# C-01_CPU_PWR.net
KiCad netlist of a schematic drawn in Altium Designer
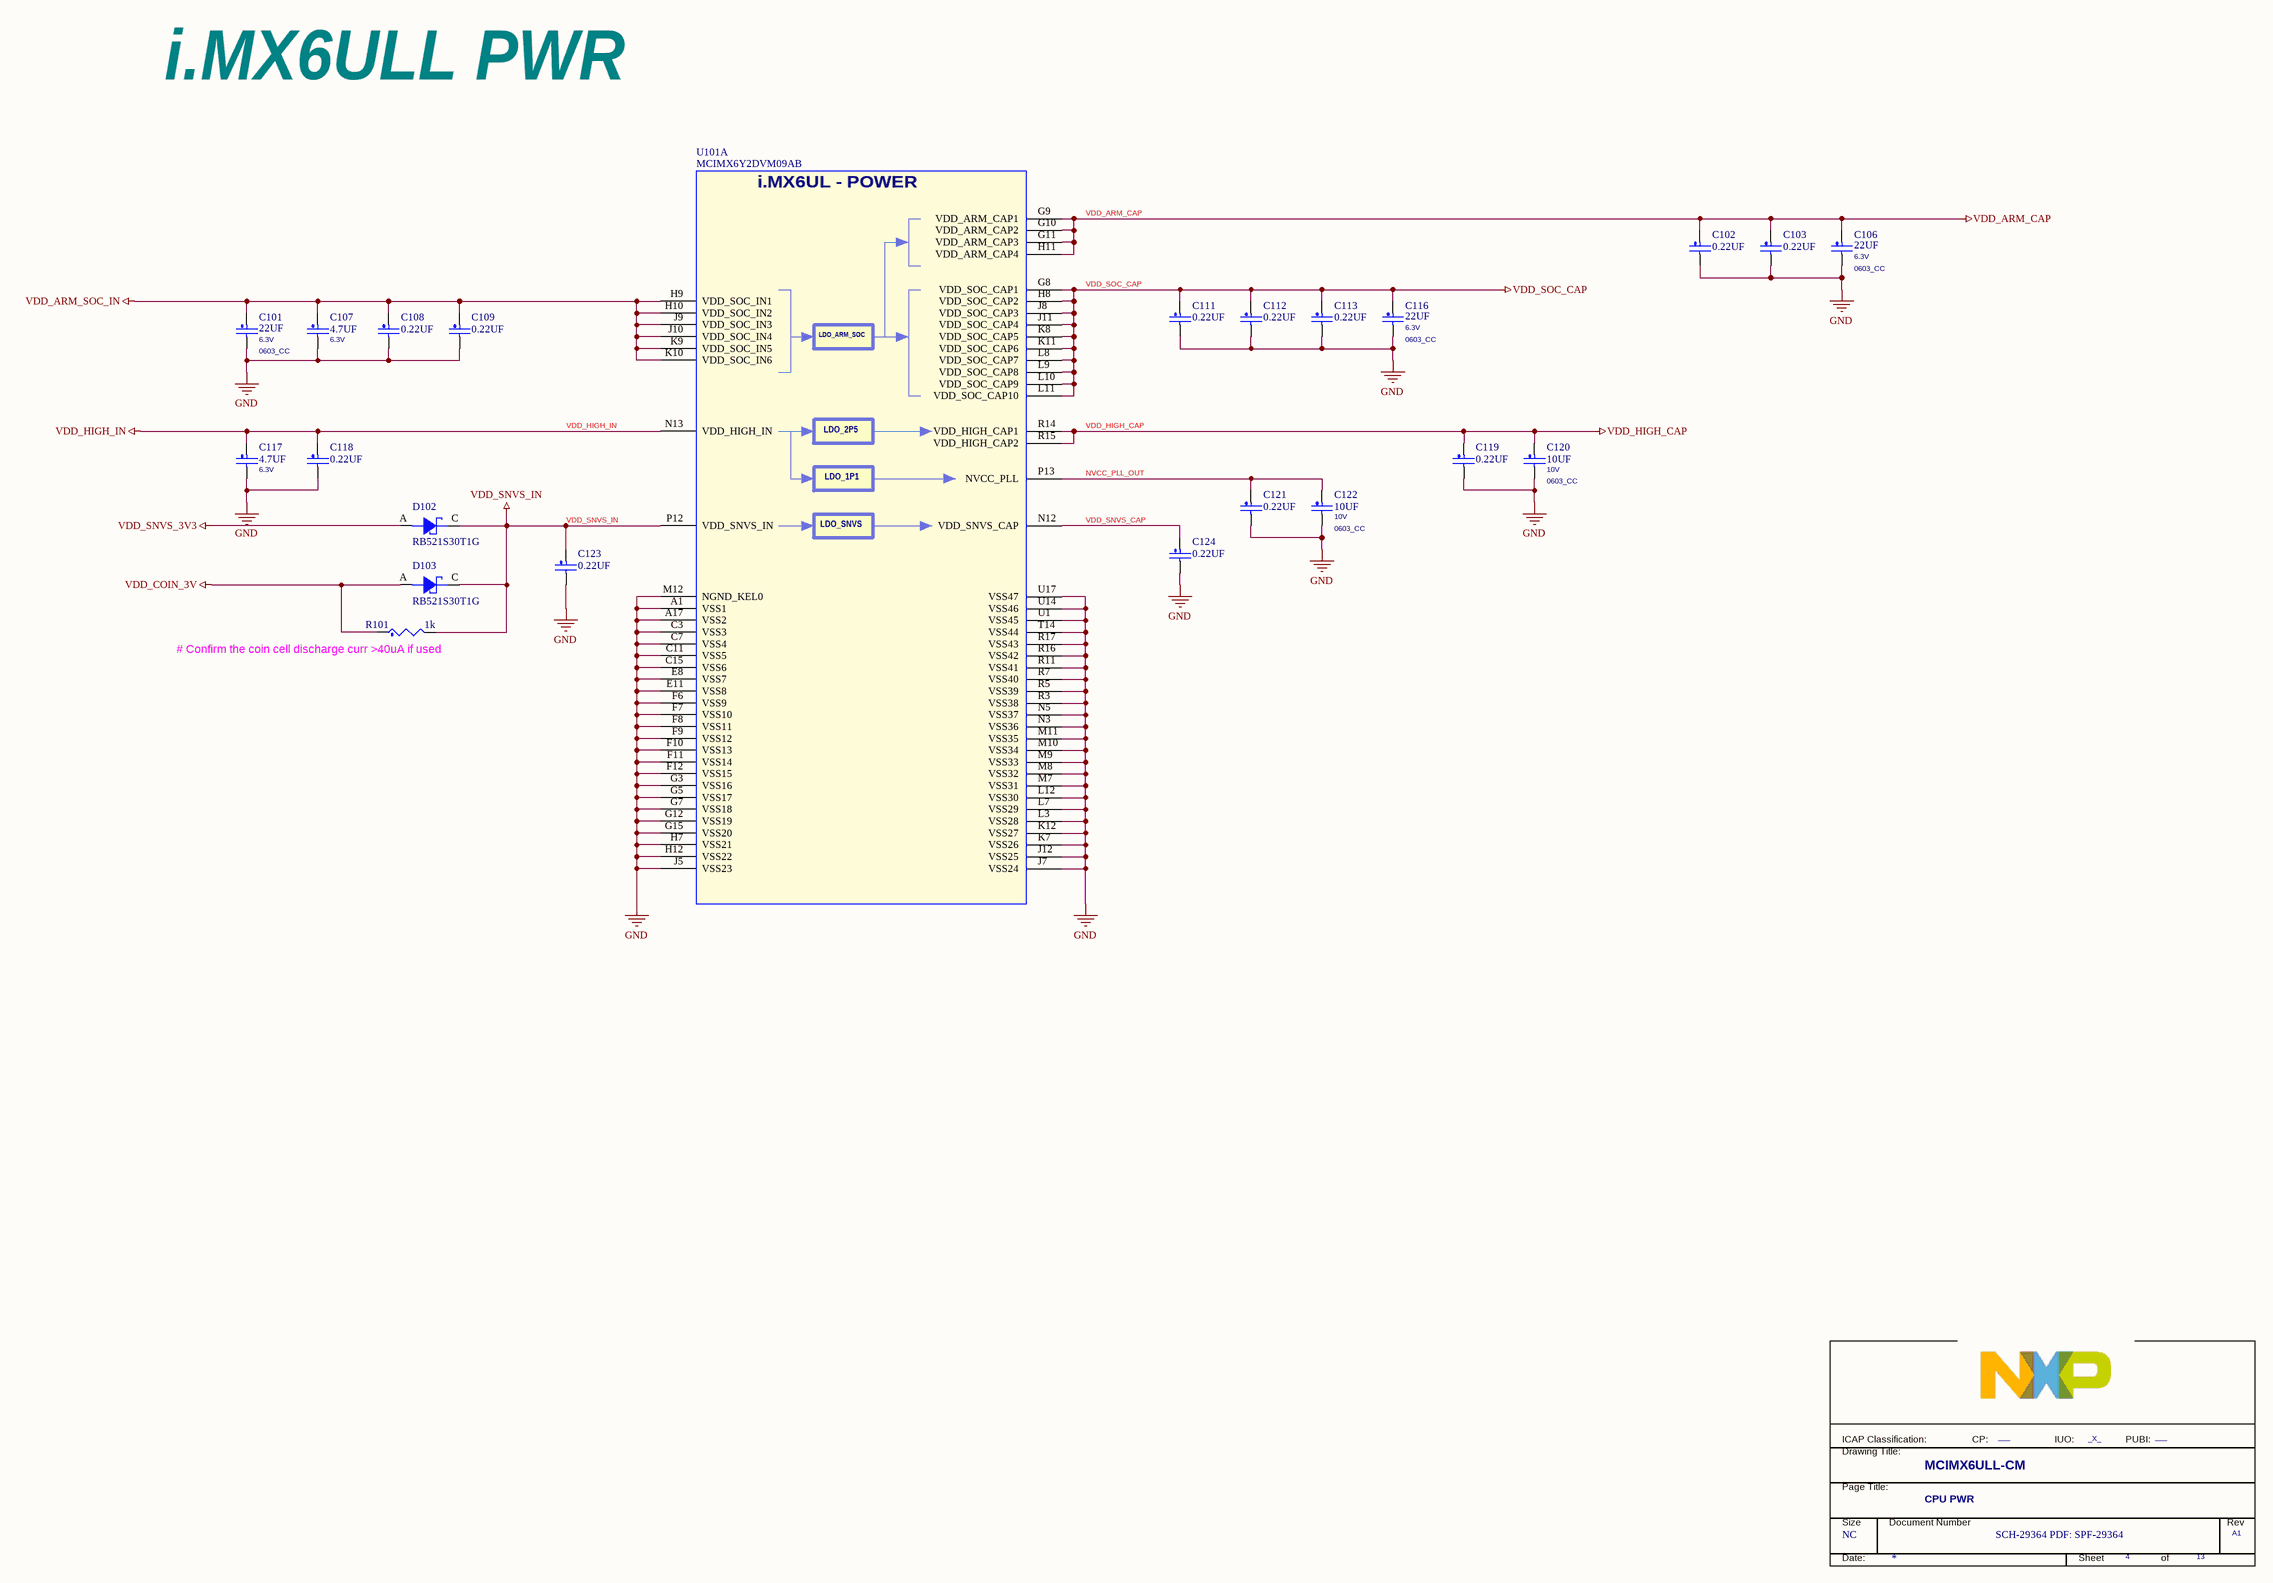
[diagram p0: C-01 CPU PWR.SchDoc]

(export (version "E")
  (design (tool "Eeschema 10.0.6"))
  (components
    (comp (ref "*")
      (value "TitleBlock_FS")
      (fields
        (field (name "PAGETITLE") "CPU PWR")
        (field (name "PAGE COUNT") "13")
        (field (name "PAGE NUMBER") "4")
        (field (name "PAGE SIZE") "NC")
        (field (name "TITLE") "MCIMX6ULL-CM")
        (field (name "REVCODE") "A1")
        (field (name "DOC") "SCH-29364 PDF: SPF-29364")
        (field (name "FCP") "___")
        (field (name "PUBI") "___")
        (field (name "FIUO") "_X_")
      )
      (libsource (lib "*") (part "TitleBlock_FS"))
    )
    (comp (ref "C101")
      (value "22UF")
      (footprint "0603_CC")
      (description "CAP CER 22UF 6.3V 20% X5R 0603")
      (fields
        (field (name "VOLTAGE RATING") "6.3V")
        (field (name "TOLERANCE") "20%")
        (field (name "VOLTAGE") "6.3V")
        (field (name "PCB FOOTPRINT") "0603_CC")
      )
      (libsource (lib "*") (part "CAP_NP"))
    )
    (comp (ref "C102")
      (value "0.22UF")
      (footprint "0402T_C")
      (description "CAP CER 0.22UF 6.3V 20% X5R 0402")
      (fields (field (name "TOLERANCE") "20%") (field (name "VOLTAGE") "6.3V"))
      (libsource (lib "*") (part "CAP_NP"))
    )
    (comp (ref "C103")
      (value "0.22UF")
      (footprint "0402T_C")
      (description "CAP CER 0.22UF 6.3V 20% X5R 0402")
      (fields (field (name "TOLERANCE") "20%") (field (name "VOLTAGE") "6.3V"))
      (libsource (lib "*") (part "CAP_NP"))
    )
    (comp (ref "C106")
      (value "22UF")
      (footprint "0402T_C")
      (description "CAP CER 22UF 6.3V 20% X5R 0603")
      (fields
        (field (name "TOLERANCE") "20%")
        (field (name "VOLTAGE") "6.3V")
        (field (name "PCB FOOTPRINT") "0603_CC")
      )
      (libsource (lib "*") (part "CAP_NP"))
    )
    (comp (ref "C107")
      (value "4.7UF")
      (footprint "0402T_C")
      (description "CAP CER 4.7UF 6.3V 20% X5R 0402")
      (fields
        (field (name "VOLTAGE") "6.3V")
        (field (name "VOLTAGE RATING") "6.3V")
        (field (name "TOLERANCE") "20%")
      )
      (libsource (lib "*") (part "CAP_NP"))
    )
    (comp (ref "C108")
      (value "0.22UF")
      (footprint "0402T_C")
      (description "CAP CER 0.22UF 6.3V 20% X5R 0402")
      (fields (field (name "TOLERANCE") "20%") (field (name "VOLTAGE") "6.3V"))
      (libsource (lib "*") (part "CAP_NP"))
    )
    (comp (ref "C109")
      (value "0.22UF")
      (footprint "0402T_C")
      (description "CAP CER 0.22UF 6.3V 20% X5R 0402")
      (fields (field (name "TOLERANCE") "20%") (field (name "VOLTAGE") "6.3V"))
      (libsource (lib "*") (part "CAP_NP"))
    )
    (comp (ref "C111")
      (value "0.22UF")
      (footprint "0402T_C")
      (description "CAP CER 0.22UF 6.3V 20% X5R 0402")
      (fields (field (name "VOLTAGE") "6.3V") (field (name "TOLERANCE") "20%"))
      (libsource (lib "*") (part "CAP_NP"))
    )
    (comp (ref "C112")
      (value "0.22UF")
      (footprint "0402T_C")
      (description "CAP CER 0.22UF 6.3V 20% X5R 0402")
      (fields (field (name "VOLTAGE") "6.3V") (field (name "TOLERANCE") "20%"))
      (libsource (lib "*") (part "CAP_NP"))
    )
    (comp (ref "C113")
      (value "0.22UF")
      (footprint "0402T_C")
      (description "CAP CER 0.22UF 6.3V 20% X5R 0402")
      (fields (field (name "VOLTAGE") "6.3V") (field (name "TOLERANCE") "20%"))
      (libsource (lib "*") (part "CAP_NP"))
    )
    (comp (ref "C116")
      (value "22UF")
      (footprint "0603_CC")
      (description "CAP CER 22UF 6.3V 20% X5R 0603")
      (fields
        (field (name "VOLTAGE") "6.3V")
        (field (name "TOLERANCE") "20%")
        (field (name "PCB FOOTPRINT") "0603_CC")
      )
      (libsource (lib "*") (part "CAP_NP"))
    )
    (comp (ref "C117")
      (value "4.7UF")
      (footprint "0402T_C")
      (description "CAP CER 4.7UF 6.3V 20% X5R 0402")
      (fields
        (field (name "VOLTAGE") "6.3V")
        (field (name "VOLTAGE RATING") "6.3V")
        (field (name "TOLERANCE") "20%")
      )
      (libsource (lib "*") (part "CAP_NP"))
    )
    (comp (ref "C118")
      (value "0.22UF")
      (footprint "0402T_C")
      (description "CAP CER 0.22UF 6.3V 20% X5R 0402")
      (fields (field (name "TOLERANCE") "20%") (field (name "VOLTAGE") "6.3V"))
      (libsource (lib "*") (part "CAP_NP"))
    )
    (comp (ref "C119")
      (value "0.22UF")
      (footprint "0402T_C")
      (description "CAP CER 0.22UF 6.3V 20% X5R 0402")
      (fields (field (name "TOLERANCE") "20%") (field (name "VOLTAGE") "6.3V"))
      (libsource (lib "*") (part "CAP_NP"))
    )
    (comp (ref "C120")
      (value "10UF")
      (footprint "0603_CC")
      (description "CAP CER 10UF 10V 20% X5R 0603")
      (fields (field (name "VOLTAGE") "10V") (field (name "PCB FOOTPRINT") "0603_CC"))
      (libsource (lib "*") (part "CAP_NP"))
    )
    (comp (ref "C121")
      (value "0.22UF")
      (footprint "0402T_C")
      (description "CAP CER 0.22UF 6.3V 20% X5R 0402")
      (fields (field (name "VOLTAGE") "6.3V") (field (name "TOLERANCE") "20%"))
      (libsource (lib "*") (part "CAP_NP"))
    )
    (comp (ref "C122")
      (value "10UF")
      (footprint "0603_CC")
      (description "CAP CER 10UF 10V 20% X5R 0603")
      (fields (field (name "VOLTAGE") "10V") (field (name "PCB FOOTPRINT") "0603_CC"))
      (libsource (lib "*") (part "CAP_NP"))
    )
    (comp (ref "C123")
      (value "0.22UF")
      (footprint "0402T_C")
      (description "CAP CER 0.22UF 6.3V 20% X5R 0402")
      (fields (field (name "TOLERANCE") "20%") (field (name "VOLTAGE") "6.3V"))
      (libsource (lib "*") (part "CAP_NP"))
    )
    (comp (ref "C124")
      (value "0.22UF")
      (footprint "0402T_C")
      (description "CAP CER 0.22UF 6.3V 20% X5R 0402")
      (fields (field (name "VOLTAGE") "6.3V") (field (name "TOLERANCE") "20%"))
      (libsource (lib "*") (part "CAP_NP"))
    )
    (comp (ref "D102")
      (value "RB521S30T1G")
      (footprint "SOD-523")
      (description "DIODE SCH 200MA 30V AEC-Q101 SOD-523")
      (libsource (lib "*") (part "DIODE_SCHTKY"))
    )
    (comp (ref "D103")
      (value "RB521S30T1G")
      (footprint "SOD-523")
      (description "DIODE SCH 200MA 30V AEC-Q101 SOD-523")
      (libsource (lib "*") (part "DIODE_SCHTKY"))
    )
    (comp (ref "R101")
      (value "1k")
      (footprint "0402T_C")
      (description "RES MF 1.0K 1/16W 5% 0402")
      (fields (field (name "TOLERANCE") "5%"))
      (libsource (lib "*") (part "RES"))
    )
    (comp (ref "U101")
      (value "MCIMX6Y2DVM09AB")
      (footprint "BGA289_0P8_14X14")
      (description "IC CPU ARM COREA7 900MHZ 16BIT 3-3.6V PBGA289")
      (libsource (lib "*") (part "MCIMX6Y2DVM05AA_PBGA_289P"))
    )
  )
  (nets
    (net (code "1") (name "/NVCC_PLL_OUT") (class "Default")
      (node (ref "C121") (pin "1") (pinfunction "1_1") (pintype "passive"))
      (node (ref "C122") (pin "1") (pinfunction "1_1") (pintype "passive"))
      (node (ref "U101") (pin "P13") (pinfunction "NVCC_PLL_P13") (pintype "power_in"))
    )
    (net (code "2") (name "/VDD_SNVS_CAP") (class "Default")
      (node (ref "C124") (pin "1") (pinfunction "1_1") (pintype "passive"))
      (node (ref "U101") (pin "N12") (pinfunction "VDD_SNVS_CAP_N12") (pintype "power_in"))
    )
    (net (code "3") (name "GND") (class "Default")
      (node (ref "C101") (pin "2") (pinfunction "2_2") (pintype "passive"))
      (node (ref "C102") (pin "2") (pinfunction "2_2") (pintype "passive"))
      (node (ref "C103") (pin "2") (pinfunction "2_2") (pintype "passive"))
      (node (ref "C106") (pin "2") (pinfunction "2_2") (pintype "passive"))
      (node (ref "C107") (pin "2") (pinfunction "2_2") (pintype "passive"))
      (node (ref "C108") (pin "2") (pinfunction "2_2") (pintype "passive"))
      (node (ref "C109") (pin "2") (pinfunction "2_2") (pintype "passive"))
      (node (ref "C111") (pin "2") (pinfunction "2_2") (pintype "passive"))
      (node (ref "C112") (pin "2") (pinfunction "2_2") (pintype "passive"))
      (node (ref "C113") (pin "2") (pinfunction "2_2") (pintype "passive"))
      (node (ref "C116") (pin "2") (pinfunction "2_2") (pintype "passive"))
      (node (ref "C117") (pin "2") (pinfunction "2_2") (pintype "passive"))
      (node (ref "C118") (pin "2") (pinfunction "2_2") (pintype "passive"))
      (node (ref "C119") (pin "2") (pinfunction "2_2") (pintype "passive"))
      (node (ref "C120") (pin "2") (pinfunction "2_2") (pintype "passive"))
      (node (ref "C121") (pin "2") (pinfunction "2_2") (pintype "passive"))
      (node (ref "C122") (pin "2") (pinfunction "2_2") (pintype "passive"))
      (node (ref "C123") (pin "2") (pinfunction "2_2") (pintype "passive"))
      (node (ref "C124") (pin "2") (pinfunction "2_2") (pintype "passive"))
      (node (ref "U101") (pin "A1") (pinfunction "VSS1_A1") (pintype "power_in"))
      (node (ref "U101") (pin "A17") (pinfunction "VSS2_A17") (pintype "power_in"))
      (node (ref "U101") (pin "C11") (pinfunction "VSS5_C11") (pintype "power_in"))
      (node (ref "U101") (pin "C15") (pinfunction "VSS6_C15") (pintype "power_in"))
      (node (ref "U101") (pin "C3") (pinfunction "VSS3_C3") (pintype "power_in"))
      (node (ref "U101") (pin "C7") (pinfunction "VSS4_C7") (pintype "power_in"))
      (node (ref "U101") (pin "E11") (pinfunction "VSS8_E11") (pintype "power_in"))
      (node (ref "U101") (pin "E8") (pinfunction "VSS7_E8") (pintype "power_in"))
      (node (ref "U101") (pin "F10") (pinfunction "VSS13_F10") (pintype "power_in"))
      (node (ref "U101") (pin "F11") (pinfunction "VSS14_F11") (pintype "power_in"))
      (node (ref "U101") (pin "F12") (pinfunction "VSS15_F12") (pintype "power_in"))
      (node (ref "U101") (pin "F6") (pinfunction "VSS9_F6") (pintype "power_in"))
      (node (ref "U101") (pin "F7") (pinfunction "VSS10_F7") (pintype "power_in"))
      (node (ref "U101") (pin "F8") (pinfunction "VSS11_F8") (pintype "power_in"))
      (node (ref "U101") (pin "F9") (pinfunction "VSS12_F9") (pintype "power_in"))
      (node (ref "U101") (pin "G12") (pinfunction "VSS19_G12") (pintype "power_in"))
      (node (ref "U101") (pin "G15") (pinfunction "VSS20_G15") (pintype "power_in"))
      (node (ref "U101") (pin "G3") (pinfunction "VSS16_G3") (pintype "power_in"))
      (node (ref "U101") (pin "G5") (pinfunction "VSS17_G5") (pintype "power_in"))
      (node (ref "U101") (pin "G7") (pinfunction "VSS18_G7") (pintype "power_in"))
      (node (ref "U101") (pin "H12") (pinfunction "VSS22_H12") (pintype "power_in"))
      (node (ref "U101") (pin "H7") (pinfunction "VSS21_H7") (pintype "power_in"))
      (node (ref "U101") (pin "J12") (pinfunction "VSS25_J12") (pintype "power_in"))
      (node (ref "U101") (pin "J5") (pinfunction "VSS23_J5") (pintype "power_in"))
      (node (ref "U101") (pin "J7") (pinfunction "VSS24_J7") (pintype "power_in"))
      (node (ref "U101") (pin "K12") (pinfunction "VSS27_K12") (pintype "power_in"))
      (node (ref "U101") (pin "K7") (pinfunction "VSS26_K7") (pintype "power_in"))
      (node (ref "U101") (pin "L12") (pinfunction "VSS30_L12") (pintype "power_in"))
      (node (ref "U101") (pin "L3") (pinfunction "VSS28_L3") (pintype "power_in"))
      (node (ref "U101") (pin "L7") (pinfunction "VSS29_L7") (pintype "power_in"))
      (node (ref "U101") (pin "M10") (pinfunction "VSS34_M10") (pintype "power_in"))
      (node (ref "U101") (pin "M11") (pinfunction "VSS35_M11") (pintype "power_in"))
      (node (ref "U101") (pin "M12") (pinfunction "NGND_KEL0_M12") (pintype "power_in"))
      (node (ref "U101") (pin "M7") (pinfunction "VSS31_M7") (pintype "power_in"))
      (node (ref "U101") (pin "M8") (pinfunction "VSS32_M8") (pintype "power_in"))
      (node (ref "U101") (pin "M9") (pinfunction "VSS33_M9") (pintype "power_in"))
      (node (ref "U101") (pin "N3") (pinfunction "VSS36_N3") (pintype "power_in"))
      (node (ref "U101") (pin "N5") (pinfunction "VSS37_N5") (pintype "power_in"))
      (node (ref "U101") (pin "R11") (pinfunction "VSS41_R11") (pintype "power_in"))
      (node (ref "U101") (pin "R16") (pinfunction "VSS42_R16") (pintype "power_in"))
      (node (ref "U101") (pin "R17") (pinfunction "VSS43_R17") (pintype "power_in"))
      (node (ref "U101") (pin "R3") (pinfunction "VSS38_R3") (pintype "power_in"))
      (node (ref "U101") (pin "R5") (pinfunction "VSS39_R5") (pintype "power_in"))
      (node (ref "U101") (pin "R7") (pinfunction "VSS40_R7") (pintype "power_in"))
      (node (ref "U101") (pin "T14") (pinfunction "VSS44_T14") (pintype "power_in"))
      (node (ref "U101") (pin "U1") (pinfunction "VSS45_U1") (pintype "power_in"))
      (node (ref "U101") (pin "U14") (pinfunction "VSS46_U14") (pintype "power_in"))
      (node (ref "U101") (pin "U17") (pinfunction "VSS47_U17") (pintype "power_in"))
    )
    (net (code "4") (name "VDD_ARM_CAP") (class "Default")
      (node (ref "C102") (pin "1") (pinfunction "1_1") (pintype "passive"))
      (node (ref "C103") (pin "1") (pinfunction "1_1") (pintype "passive"))
      (node (ref "C106") (pin "1") (pinfunction "1_1") (pintype "passive"))
      (node (ref "U101") (pin "G10") (pinfunction "VDD_ARM_CAP2_G10") (pintype "power_in"))
      (node (ref "U101") (pin "G11") (pinfunction "VDD_ARM_CAP3_G11") (pintype "power_in"))
      (node (ref "U101") (pin "G9") (pinfunction "VDD_ARM_CAP1_G9") (pintype "power_in"))
      (node (ref "U101") (pin "H11") (pinfunction "VDD_ARM_CAP4_H11") (pintype "power_in"))
    )
    (net (code "5") (name "VDD_ARM_SOC_IN") (class "Default")
      (node (ref "C101") (pin "1") (pinfunction "1_1") (pintype "passive"))
      (node (ref "C107") (pin "1") (pinfunction "1_1") (pintype "passive"))
      (node (ref "C108") (pin "1") (pinfunction "1_1") (pintype "passive"))
      (node (ref "C109") (pin "1") (pinfunction "1_1") (pintype "passive"))
      (node (ref "U101") (pin "H10") (pinfunction "VDD_SOC_IN2_H10") (pintype "power_in"))
      (node (ref "U101") (pin "H9") (pinfunction "VDD_SOC_IN1_H9") (pintype "power_in"))
      (node (ref "U101") (pin "J10") (pinfunction "VDD_SOC_IN4_J10") (pintype "power_in"))
      (node (ref "U101") (pin "J9") (pinfunction "VDD_SOC_IN3_J9") (pintype "power_in"))
      (node (ref "U101") (pin "K10") (pinfunction "VDD_SOC_IN6_K10") (pintype "power_in"))
      (node (ref "U101") (pin "K9") (pinfunction "VDD_SOC_IN5_K9") (pintype "power_in"))
    )
    (net (code "6") (name "VDD_COIN_3V") (class "Default")
      (node (ref "D103") (pin "A") (pinfunction "A_A") (pintype "passive"))
      (node (ref "R101") (pin "1") (pinfunction "1_1") (pintype "passive"))
    )
    (net (code "7") (name "VDD_HIGH_CAP") (class "Default")
      (node (ref "C119") (pin "1") (pinfunction "1_1") (pintype "passive"))
      (node (ref "C120") (pin "1") (pinfunction "1_1") (pintype "passive"))
      (node (ref "U101") (pin "R14") (pinfunction "VDD_HIGH_CAP1_R14") (pintype "power_in"))
      (node (ref "U101") (pin "R15") (pinfunction "VDD_HIGH_CAP2_R15") (pintype "power_in"))
    )
    (net (code "8") (name "VDD_HIGH_IN") (class "Default")
      (node (ref "C117") (pin "1") (pinfunction "1_1") (pintype "passive"))
      (node (ref "C118") (pin "1") (pinfunction "1_1") (pintype "passive"))
      (node (ref "U101") (pin "N13") (pinfunction "VDD_HIGH_IN_N13") (pintype "power_in"))
    )
    (net (code "9") (name "VDD_SNVS_3V3") (class "Default")
      (node (ref "D102") (pin "A") (pinfunction "A_A") (pintype "passive"))
    )
    (net (code "10") (name "VDD_SNVS_IN") (class "Default")
      (node (ref "C123") (pin "1") (pinfunction "1_1") (pintype "passive"))
      (node (ref "D102") (pin "C") (pinfunction "C_C") (pintype "passive"))
      (node (ref "D103") (pin "C") (pinfunction "C_C") (pintype "passive"))
      (node (ref "R101") (pin "2") (pinfunction "2_2") (pintype "passive"))
      (node (ref "U101") (pin "P12") (pinfunction "VDD_SNVS_IN_P12") (pintype "power_in"))
    )
    (net (code "11") (name "VDD_SOC_CAP") (class "Default")
      (node (ref "C111") (pin "1") (pinfunction "1_1") (pintype "passive"))
      (node (ref "C112") (pin "1") (pinfunction "1_1") (pintype "passive"))
      (node (ref "C113") (pin "1") (pinfunction "1_1") (pintype "passive"))
      (node (ref "C116") (pin "1") (pinfunction "1_1") (pintype "passive"))
      (node (ref "U101") (pin "G8") (pinfunction "VDD_SOC_CAP1_G8") (pintype "power_in"))
      (node (ref "U101") (pin "H8") (pinfunction "VDD_SOC_CAP2_H8") (pintype "power_in"))
      (node (ref "U101") (pin "J11") (pinfunction "VDD_SOC_CAP4_J11") (pintype "power_in"))
      (node (ref "U101") (pin "J8") (pinfunction "VDD_SOC_CAP3_J8") (pintype "power_in"))
      (node (ref "U101") (pin "K11") (pinfunction "VDD_SOC_CAP6_K11") (pintype "power_in"))
      (node (ref "U101") (pin "K8") (pinfunction "VDD_SOC_CAP5_K8") (pintype "power_in"))
      (node (ref "U101") (pin "L10") (pinfunction "VDD_SOC_CAP9_L10") (pintype "power_in"))
      (node (ref "U101") (pin "L11") (pinfunction "VDD_SOC_CAP10_L11") (pintype "power_in"))
      (node (ref "U101") (pin "L8") (pinfunction "VDD_SOC_CAP7_L8") (pintype "power_in"))
      (node (ref "U101") (pin "L9") (pinfunction "VDD_SOC_CAP8_L9") (pintype "power_in"))
    )
  )
)
